# Boost_12V.net
KiCad netlist of a schematic drawn in Altium Designer
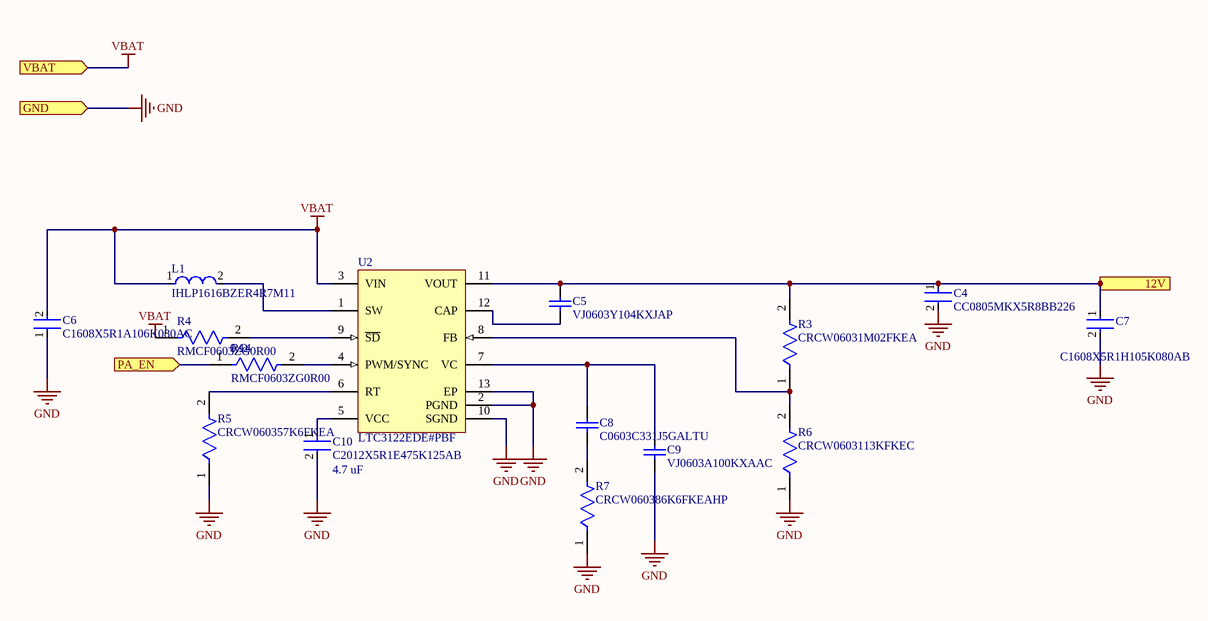
[diagram p0: Boost 12V.SchDoc]

(export (version "E")
  (design (tool "Eeschema 10.0.6"))
  (components
    (comp (ref "C4")
      (value "CC0805MKX5R8BB226")
      (footprint "FP-CC0805-0_2-1_45-IPC_C")
      (description "CAP CER 22UF 25V X5R 0805")
      (fields (field (name "TOLERANCE") "20%"))
      (libsource (lib "Altium Content Vault") (part "11868f565c42a9108669ba33697ecf6"))
    )
    (comp (ref "C5")
      (value "VJ0603Y104KXJAP")
      (footprint "CAPC1608X92X38NL15T08")
      (fields (field (name "MANUFACTURER") "Vitramon"))
      (libsource (lib "Altium Content Vault") (part "CAP"))
    )
    (comp (ref "C6")
      (value "C1608X5R1A106K080AC")
      (footprint "FP-C1608-080-0_1-MFG")
      (description "Multilayer Ceramic Capacitors 10μF ±10% 10V X5R SMD 0603")
      (fields (field (name "VOLTAGE") "10V") (field (name "TOLERANCE") "10%"))
      (libsource (lib "Altium Content Vault") (part "236180d848d6139a670b325ea6854c9"))
    )
    (comp (ref "C7")
      (value "C1608X5R1H105K080AB")
      (footprint "FP-C1608-080-0_1-IPC_B")
      (description "Multilayer Ceramic Capacitors 1μF ±10% 50V X5R SMD 0603")
      (fields (field (name "VOLTAGE") "50V") (field (name "TOLERANCE") "10%"))
      (libsource (lib "Altium Content Vault") (part "236180d848d6139a670b325ea6854c9"))
    )
    (comp (ref "C8")
      (value "C0603C331J5GALTU")
      (footprint "CAPC1608X87X35NL15T15")
      (fields (field (name "MANUFACTURER") "Kemet"))
      (libsource (lib "Altium Content Vault") (part "CAP"))
    )
    (comp (ref "C9")
      (value "VJ0603A100KXAAC")
      (footprint "CAPC1608X92X38ML12T08")
      (fields (field (name "MANUFACTURER") "Vitramon"))
      (libsource (lib "Altium Content Vault") (part "CAP"))
    )
    (comp (ref "C10")
      (value "C2012X5R1E475K125AB")
      (footprint "FP-C2012-125-0_2-MFG")
      (description "Multilayer Ceramic Capacitors 4.7μF ±10% 25V X5R SMD 0805")
      (fields (field (name "VOLTAGE") "25V") (field (name "TOLERANCE") "10%"))
      (libsource (lib "Altium Content Vault") (part "b4654b650e69147ec39a6b967a45e02"))
    )
    (comp (ref "L1")
      (value "IHLP1616BZER4R7M11")
      (footprint "FP-IHLP-1616BZ-FP_1_8545x-MFG")
      (description "Fixed Inductors Commercial Low DCR Series SMT 4.7uH 1.7A 105mΩ 20%")
      (fields (field (name "TOLERANCE") "20%"))
      (libsource (lib "Altium Content Vault") (part "725321dda6339637d4d059423bc1c3c"))
    )
    (comp (ref "R3")
      (value "CRCW06031M02FKEA")
      (footprint "FP-CRCW0603-e3-IPC_A")
      (description "RES Thick Film, 1.02MΩ, 1%, 0.1W, 100ppm/°C, 0603")
      (fields (field (name "TOLERANCE") "1%"))
      (libsource (lib "Altium Content Vault") (part "1029c3af85768c4190bb7ad29bc67b5"))
    )
    (comp (ref "R4")
      (value "RMCF0603ZG0R00")
      (footprint "FP-RMCF0603-IPC_B")
      (description "0Ω ±0 0.1W 0603 Thick Film Chip Resistor AEC-Q200 compliant")
      (libsource (lib "Altium Content Vault") (part "1029c3af85768c4190bb7ad29bc67b5"))
    )
    (comp (ref "R5")
      (value "CRCW060357K6FKEA")
      (footprint "FP-CRCW0603-e3-MFG")
      (description "RES Thick Film, 57.6kΩ, 1%, 0.1W, 100ppm/°C, 0603")
      (fields (field (name "TOLERANCE") "1%"))
      (libsource (lib "Altium Content Vault") (part "1029c3af85768c4190bb7ad29bc67b5"))
    )
    (comp (ref "R6")
      (value "CRCW0603113KFKEC")
      (footprint "FP-CRCW0603-e3-MFG")
      (description "RES Thick Film, 113kΩ, 1%, 0.1W, 100ppm/°C, 0603")
      (fields (field (name "TOLERANCE") "1%"))
      (libsource (lib "Altium Content Vault") (part "1029c3af85768c4190bb7ad29bc67b5"))
    )
    (comp (ref "R7")
      (value "CRCW060386K6FKEAHP")
      (footprint "FP-CRCW0603-HPe3-MFG")
      (description "RES Thick Film, 86.6kΩ, 1%, 0.33W, 100ppm/°C, 0603")
      (fields (field (name "TOLERANCE") "1%"))
      (libsource (lib "Altium Content Vault") (part "1029c3af85768c4190bb7ad29bc67b5"))
    )
    (comp (ref "R14")
      (value "RMCF0603ZG0R00")
      (footprint "FP-RMCF0603-IPC_B")
      (description "0Ω ±0 0.1W 0603 Thick Film Chip Resistor AEC-Q200 compliant")
      (libsource (lib "Altium Content Vault") (part "1029c3af85768c4190bb7ad29bc67b5"))
    )
    (comp (ref "U2")
      (value "LTC3122EDE#PBF")
      (footprint "LT-DE-UE-12_V")
      (fields (field (name "MANUFACTURER") "Linear Technology"))
      (libsource (lib "Altium Content Vault") (part "LT-LTC3122-X-12"))
    )
  )
  (nets
    (net (code "1") (name "/12V") (class "Default")
      (node (ref "C4") (pin "1") (pinfunction "1_1") (pintype "passive"))
      (node (ref "C5") (pin "2") (pinfunction "2_2") (pintype "passive"))
      (node (ref "C7") (pin "1") (pinfunction "1_1") (pintype "passive"))
      (node (ref "R3") (pin "2") (pinfunction "2_2") (pintype "passive"))
      (node (ref "U2") (pin "11") (pinfunction "VOUT_11") (pintype "power_in"))
    )
    (net (code "2") (name "/PA_EN") (class "Default")
      (node (ref "R14") (pin "1") (pinfunction "1_1") (pintype "passive"))
    )
    (net (code "3") (name "GND") (class "Default")
      (node (ref "C10") (pin "2") (pinfunction "2_2") (pintype "passive"))
      (node (ref "C4") (pin "2") (pinfunction "2_2") (pintype "passive"))
      (node (ref "C6") (pin "1") (pinfunction "1_1") (pintype "passive"))
      (node (ref "C7") (pin "2") (pinfunction "2_2") (pintype "passive"))
      (node (ref "C9") (pin "1") (pinfunction "1_1") (pintype "passive"))
      (node (ref "R5") (pin "1") (pinfunction "1_1") (pintype "passive"))
      (node (ref "R6") (pin "1") (pinfunction "1_1") (pintype "passive"))
      (node (ref "R7") (pin "1") (pinfunction "1_1") (pintype "passive"))
      (node (ref "U2") (pin "10") (pinfunction "SGND_10") (pintype "power_in"))
      (node (ref "U2") (pin "13") (pinfunction "EP_13") (pintype "power_in"))
      (node (ref "U2") (pin "2") (pinfunction "PGND_2") (pintype "power_in"))
    )
    (net (code "4") (name "Net-(C8-Pad1)") (class "Default")
      (node (ref "C8") (pin "1") (pinfunction "1_1") (pintype "passive"))
      (node (ref "R7") (pin "2") (pinfunction "2_2") (pintype "passive"))
    )
    (net (code "5") (name "Net-(U2-CAP)") (class "Default")
      (node (ref "C5") (pin "1") (pinfunction "1_1") (pintype "passive"))
      (node (ref "U2") (pin "12") (pinfunction "CAP_12") (pintype "passive"))
    )
    (net (code "6") (name "Net-(U2-FB)") (class "Default")
      (node (ref "R3") (pin "1") (pinfunction "1_1") (pintype "passive"))
      (node (ref "R6") (pin "2") (pinfunction "2_2") (pintype "passive"))
      (node (ref "U2") (pin "8") (pinfunction "FB_8") (pintype "input"))
    )
    (net (code "7") (name "Net-(U2-PWM{slash}SYNC)") (class "Default")
      (node (ref "R14") (pin "2") (pinfunction "2_2") (pintype "passive"))
      (node (ref "U2") (pin "4") (pinfunction "PWM/SYNC_4") (pintype "input"))
    )
    (net (code "8") (name "Net-(U2-RT)") (class "Default")
      (node (ref "R5") (pin "2") (pinfunction "2_2") (pintype "passive"))
      (node (ref "U2") (pin "6") (pinfunction "RT_6") (pintype "passive"))
    )
    (net (code "9") (name "Net-(U2-SW)") (class "Default")
      (node (ref "L1") (pin "2") (pinfunction "2_2") (pintype "passive"))
      (node (ref "U2") (pin "1") (pinfunction "SW_1") (pintype "passive"))
    )
    (net (code "10") (name "Net-(U2-VC)") (class "Default")
      (node (ref "C8") (pin "2") (pinfunction "2_2") (pintype "passive"))
      (node (ref "C9") (pin "2") (pinfunction "2_2") (pintype "passive"))
      (node (ref "U2") (pin "7") (pinfunction "VC_7") (pintype "passive"))
    )
    (net (code "11") (name "Net-(U2-VCC)") (class "Default")
      (node (ref "C10") (pin "1") (pinfunction "1_1") (pintype "passive"))
      (node (ref "U2") (pin "5") (pinfunction "VCC_5") (pintype "power_in"))
    )
    (net (code "12") (name "Net-(U2-~{SD})") (class "Default")
      (node (ref "R4") (pin "2") (pinfunction "2_2") (pintype "passive"))
      (node (ref "U2") (pin "9") (pinfunction "~{SD}_9") (pintype "input"))
    )
    (net (code "13") (name "VBAT") (class "Default")
      (node (ref "C6") (pin "2") (pinfunction "2_2") (pintype "passive"))
      (node (ref "L1") (pin "1") (pinfunction "1_1") (pintype "passive"))
      (node (ref "R4") (pin "1") (pinfunction "1_1") (pintype "passive"))
      (node (ref "U2") (pin "3") (pinfunction "VIN_3") (pintype "power_in"))
    )
  )
)
